# VHFA_PWR_Supply.net
KiCad netlist of a schematic drawn in Altium Designer
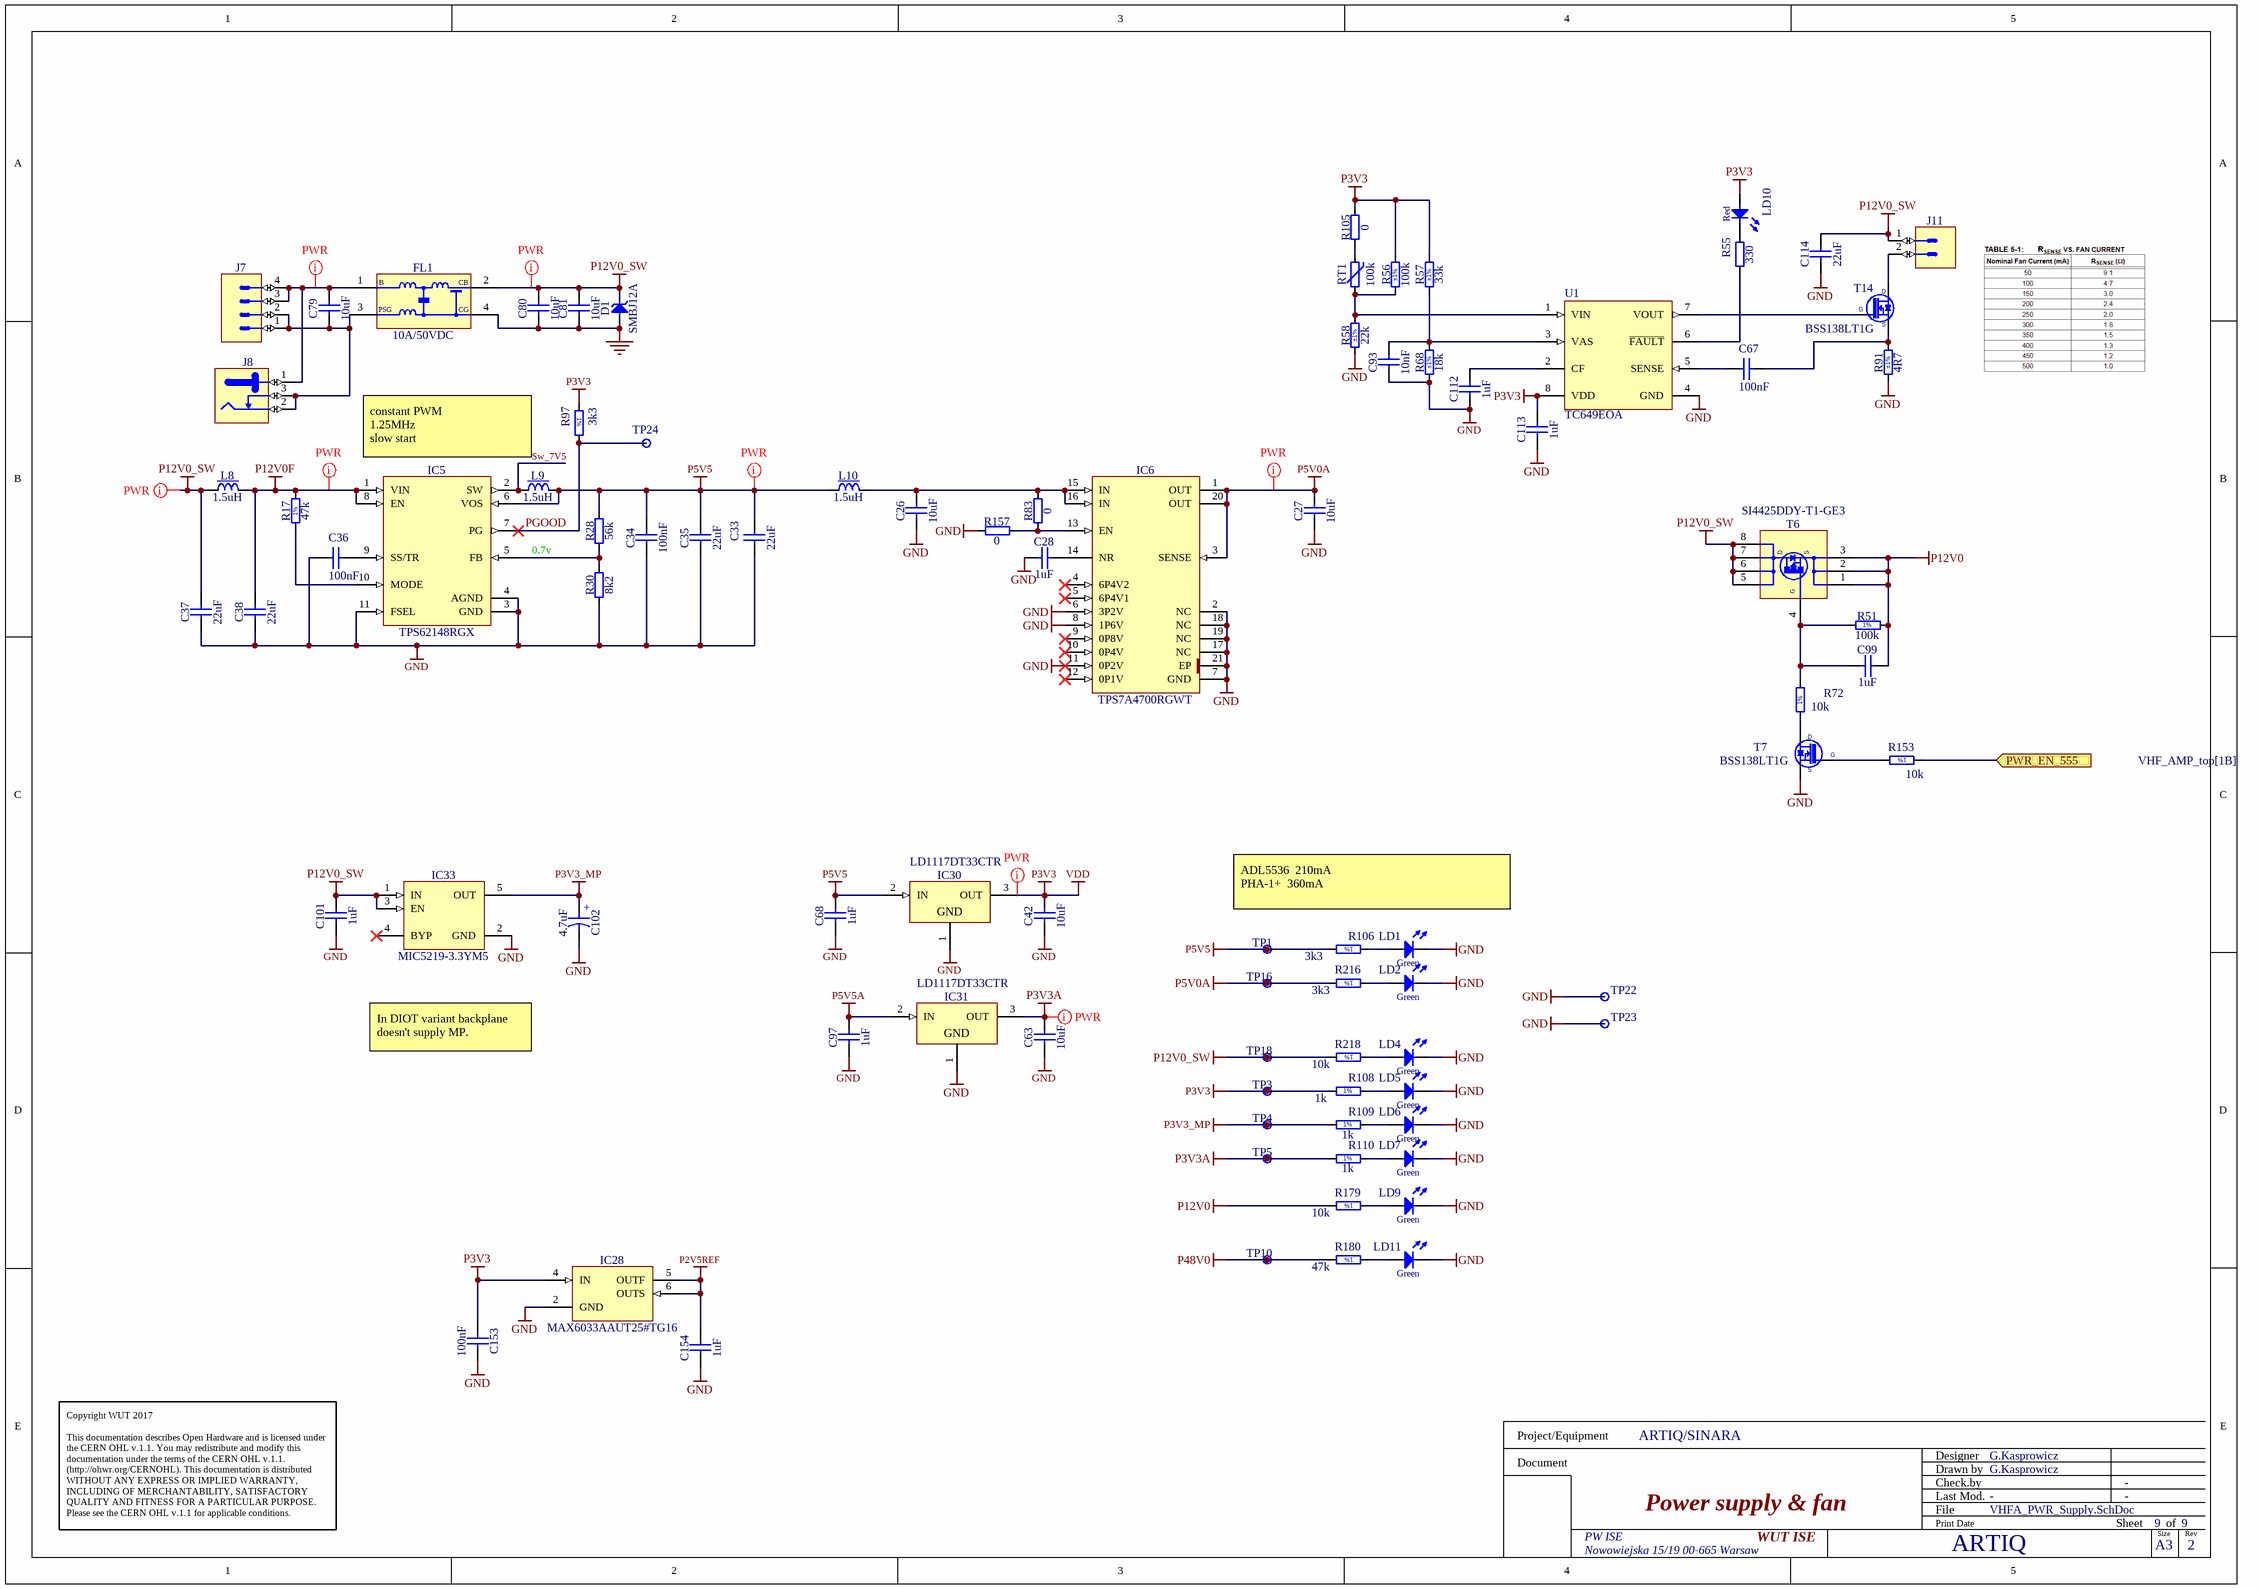
[diagram p0: VHFA_PWR_Supply.SchDoc]

(export (version "E")
  (design (tool "Eeschema 10.0.6"))
  (components
    (comp (ref "C26")
      (value "10uF")
      (footprint "CAPC3216X140N")
      (description "Non-polarised capacitor")
      (fields
        (field (name "PART NUMBER") "CC1206_10UF_10V_10%_X7R")
        (field (name "VOLTAGE") "10V")
        (field (name "AUTHOR") "CERN DEM JLC")
      )
      (libsource (lib "Capacitors") (part "Capacitor - non polarized"))
    )
    (comp (ref "C27")
      (value "10uF")
      (footprint "CAPC3216X140N")
      (description "Non-polarised capacitor")
      (fields
        (field (name "PART NUMBER") "CC1206_10UF_10V_10%_X7R")
        (field (name "VOLTAGE") "10V")
        (field (name "AUTHOR") "CERN DEM JLC")
      )
      (libsource (lib "Capacitors") (part "Capacitor - non polarized"))
    )
    (comp (ref "C28")
      (value "1uF")
      (footprint "CAPC1608X87N")
      (description "Non-polarised capacitor")
      (fields
        (field (name "PART NUMBER") "CC0603_1UF_16V_10%_X7R")
        (field (name "VOLTAGE") "16V")
        (field (name "AUTHOR") "CERN DEM JLC")
      )
      (libsource (lib "Capacitors") (part "Capacitor - non polarized"))
    )
    (comp (ref "C33")
      (value "22uF")
      (footprint "CAPC3216X180N")
      (description "Non-polarised capacitor")
      (fields
        (field (name "PART NUMBER") "CC1206_22UF_35V_20%_JB_TDK_C3216JB1V226M160AC")
        (field (name "VOLTAGE") "35V")
        (field (name "AUTHOR") "CERN DEM JLC")
      )
      (libsource (lib "Capacitors") (part "Capacitor - non polarized"))
    )
    (comp (ref "C34")
      (value "100nF")
      (footprint "CAPC1005X55N")
      (description "Non-polarised capacitor")
      (fields
        (field (name "PART NUMBER") "CC0402_100NF_16V_10%_X5R")
        (field (name "VOLTAGE") "16V")
        (field (name "AUTHOR") "CERN DEM JLC")
      )
      (libsource (lib "Capacitors") (part "Capacitor - non polarized"))
    )
    (comp (ref "C35")
      (value "22uF")
      (footprint "CAPC3216X180N")
      (description "Non-polarised capacitor")
      (fields
        (field (name "PART NUMBER") "CC1206_22UF_35V_20%_JB_TDK_C3216JB1V226M160AC")
        (field (name "VOLTAGE") "35V")
        (field (name "AUTHOR") "CERN DEM JLC")
      )
      (libsource (lib "Capacitors") (part "Capacitor - non polarized"))
    )
    (comp (ref "C36")
      (value "100nF")
      (footprint "CAPC1005X55N")
      (description "Non-polarised capacitor")
      (fields
        (field (name "PART NUMBER") "CC0402_100NF_16V_10%_X5R")
        (field (name "VOLTAGE") "16V")
        (field (name "AUTHOR") "CERN DEM JLC")
      )
      (libsource (lib "Capacitors") (part "Capacitor - non polarized"))
    )
    (comp (ref "C37")
      (value "22uF")
      (footprint "CAPC3216X180N")
      (description "Non-polarised capacitor")
      (fields
        (field (name "PART NUMBER") "CC1206_22UF_35V_20%_JB_TDK_C3216JB1V226M160AC")
        (field (name "VOLTAGE") "35V")
        (field (name "AUTHOR") "CERN DEM JLC")
      )
      (libsource (lib "Capacitors") (part "Capacitor - non polarized"))
    )
    (comp (ref "C38")
      (value "22uF")
      (footprint "CAPC3216X180N")
      (description "Non-polarised capacitor")
      (fields
        (field (name "PART NUMBER") "CC1206_22UF_35V_20%_JB_TDK_C3216JB1V226M160AC")
        (field (name "VOLTAGE") "35V")
        (field (name "AUTHOR") "CERN DEM JLC")
      )
      (libsource (lib "Capacitors") (part "Capacitor - non polarized"))
    )
    (comp (ref "C42")
      (value "10uF")
      (footprint "CAPC3216X140N")
      (description "Non-polarised capacitor")
      (fields
        (field (name "PART NUMBER") "CC1206_10UF_10V_10%_X7R")
        (field (name "VOLTAGE") "10V")
        (field (name "AUTHOR") "CERN DEM JLC")
      )
      (libsource (lib "Capacitors") (part "Capacitor - non polarized"))
    )
    (comp (ref "C63")
      (value "10uF")
      (footprint "CAPC3216X140N")
      (description "Non-polarised capacitor")
      (fields
        (field (name "PART NUMBER") "CC1206_10UF_10V_10%_X7R")
        (field (name "VOLTAGE") "10V")
        (field (name "AUTHOR") "CERN DEM JLC")
      )
      (libsource (lib "Capacitors") (part "Capacitor - non polarized"))
    )
    (comp (ref "C67")
      (value "100nF")
      (footprint "CAPC1005X55N")
      (description "Non-polarised capacitor")
      (fields
        (field (name "PART NUMBER") "CC0402_100NF_16V_10%_X5R")
        (field (name "VOLTAGE") "16V")
        (field (name "AUTHOR") "CERN DEM JLC")
      )
      (libsource (lib "Capacitors") (part "Capacitor - non polarized"))
    )
    (comp (ref "C68")
      (value "1uF")
      (footprint "CAPC1608X87N")
      (description "Non-polarised capacitor")
      (fields
        (field (name "PART NUMBER") "CC0603_1UF_16V_10%_X7R")
        (field (name "VOLTAGE") "16V")
        (field (name "AUTHOR") "CERN DEM JLC")
      )
      (libsource (lib "Capacitors") (part "Capacitor - non polarized"))
    )
    (comp (ref "C79")
      (value "10uF")
      (footprint "CAPC2012X95N")
      (description "Non-polarised capacitor")
      (fields
        (field (name "PART NUMBER") "CC0805_10UF_25V_10%_X5R")
        (field (name "VOLTAGE") "25V")
        (field (name "AUTHOR") "CERN DEM JLC")
      )
      (libsource (lib "Capacitors") (part "Capacitor - non polarized"))
    )
    (comp (ref "C80")
      (value "10uF")
      (footprint "CAPC2012X95N")
      (description "Non-polarised capacitor")
      (fields
        (field (name "PART NUMBER") "CC0805_10UF_25V_10%_X5R")
        (field (name "VOLTAGE") "25V")
        (field (name "AUTHOR") "CERN DEM JLC")
      )
      (libsource (lib "Capacitors") (part "Capacitor - non polarized"))
    )
    (comp (ref "C81")
      (value "10uF")
      (footprint "CAPC2012X95N")
      (description "Non-polarised capacitor")
      (fields
        (field (name "PART NUMBER") "CC0805_10UF_25V_10%_X5R")
        (field (name "VOLTAGE") "25V")
        (field (name "AUTHOR") "CERN DEM JLC")
      )
      (libsource (lib "Capacitors") (part "Capacitor - non polarized"))
    )
    (comp (ref "C93")
      (value "10nF")
      (footprint "CAPC1608X87N")
      (description "Non-polarised capacitor")
      (fields
        (field (name "PART NUMBER") "CC0603_10NF_50V_10%_X7R")
        (field (name "VOLTAGE") "50V")
        (field (name "AUTHOR") "CERN DEM JLC")
      )
      (libsource (lib "Capacitors") (part "Capacitor - non polarized"))
    )
    (comp (ref "C97")
      (value "1uF")
      (footprint "CAPC1608X87N")
      (description "Non-polarised capacitor")
      (fields
        (field (name "PART NUMBER") "CC0603_1UF_16V_10%_X7R")
        (field (name "VOLTAGE") "16V")
        (field (name "AUTHOR") "CERN DEM JLC")
      )
      (libsource (lib "Capacitors") (part "Capacitor - non polarized"))
    )
    (comp (ref "C99")
      (value "1uF")
      (footprint "CAPC1005X55N")
      (description "Non-polarised capacitor")
      (fields
        (field (name "PART NUMBER") "CC0402_1UF_16V_10%_X5R")
        (field (name "VOLTAGE") "16V")
        (field (name "AUTHOR") "CERN DEM JLC")
      )
      (libsource (lib "Capacitors") (part "Capacitor - non polarized"))
    )
    (comp (ref "C101")
      (value "1uF")
      (footprint "CAPC1608X87N")
      (description "Non-polarised capacitor")
      (fields
        (field (name "PART NUMBER") "CC0603_1UF_25V_10%_X7R")
        (field (name "VOLTAGE") "25V")
        (field (name "AUTHOR") "CERN DEM JLC")
      )
      (libsource (lib "Capacitors") (part "Capacitor - non polarized"))
    )
    (comp (ref "C102")
      (value "4.7uF")
      (footprint "CAPMP3216X180N")
      (description "Polarised capacitor")
      (fields
        (field (name "PART NUMBER") "CTE3216-18_4.7UF_10V_10%_AVX_TPSA475K010T1400")
        (field (name "VOLTAGE") "10V")
        (field (name "AUTHOR") "CERN DEM JLC")
      )
      (libsource (lib "Capacitors") (part "Capacitor - polarized"))
    )
    (comp (ref "C112")
      (value "1uF")
      (footprint "CAPC1608X87N")
      (description "Non-polarised capacitor")
      (fields
        (field (name "PART NUMBER") "CC0603_1UF_16V_10%_X7R")
        (field (name "VOLTAGE") "16V")
        (field (name "AUTHOR") "CERN DEM JLC")
      )
      (libsource (lib "Capacitors") (part "Capacitor - non polarized"))
    )
    (comp (ref "C113")
      (value "1uF")
      (footprint "CAPC1608X87N")
      (description "Non-polarised capacitor")
      (fields
        (field (name "PART NUMBER") "CC0603_1UF_16V_10%_X7R")
        (field (name "VOLTAGE") "16V")
        (field (name "AUTHOR") "CERN DEM JLC")
      )
      (libsource (lib "Capacitors") (part "Capacitor - non polarized"))
    )
    (comp (ref "C114")
      (value "22uF")
      (footprint "CAPC3216X180N")
      (description "Non-polarised capacitor")
      (fields
        (field (name "PART NUMBER") "CC1206_22UF_35V_20%_JB_TDK_C3216JB1V226M160AC")
        (field (name "VOLTAGE") "35V")
        (field (name "AUTHOR") "CERN DEM JLC")
      )
      (libsource (lib "Capacitors") (part "Capacitor - non polarized"))
    )
    (comp (ref "C153")
      (value "100nF")
      (footprint "CAPC1005X55N")
      (description "Non-polarised capacitor")
      (fields
        (field (name "PART NUMBER") "CC0402_100NF_16V_10%_X5R")
        (field (name "VOLTAGE") "16V")
        (field (name "AUTHOR") "CERN DEM JLC")
      )
      (libsource (lib "Capacitors") (part "Capacitor - non polarized"))
    )
    (comp (ref "C154")
      (value "1uF")
      (footprint "CAPC2012X110N")
      (description "Non-polarised capacitor")
      (fields
        (field (name "PART NUMBER") "CC0805_1UF_50V_10%_X7R")
        (field (name "VOLTAGE") "50V")
        (field (name "AUTHOR") "CERN DEM JLC")
      )
      (libsource (lib "Capacitors") (part "Capacitor - non polarized"))
    )
    (comp (ref "D1")
      (value "SMBJ12A")
      (footprint "DIOM5336X265N")
      (description "Zener Diode")
      (fields
        (field (name "VOLTAGE") "12V")
        (field (name "POWER") "600W")
        (field (name "AUTHOR") "CERN DEM JLC")
      )
      (libsource (lib "ICs And Semiconductors") (part "Diode Zener"))
    )
    (comp (ref "FL1")
      (value "10A/50VDC")
      (footprint "FIL_MURATA_BNX02")
      (description "Block Type EMIFIL (LC Combined)")
      (fields
        (field (name "PART NUMBER") "FIL_MURATA_BNX022-01L")
        (field (name "MANUFACTURER") "MURATA")
        (field (name "AUTHOR") "CERN DEM JLC")
      )
      (libsource (lib "Inductors & Transformers") (part "FIL_MURATA_BNX02"))
    )
    (comp (ref "IC5")
      (value "TPS62148RGX")
      (footprint "TEXAS_RGX0011A")
      (description "3V-17V 2A Step-Down Converter, High Accuracy, With DCS-Control")
      (fields (field (name "MANUFACTURER") "TEXAS INSTRUMENTS") (field (name "AUTHOR") "CERN DEM MR"))
      (libsource (lib "ICs And Semiconductors") (part "TPS62148"))
    )
    (comp (ref "IC6")
      (value "TPS7A4700RGWT")
      (footprint "QFN65P500X500X100-21N-S325")
      (description "Low Noise (3uVrms), 1A, High Voltage Low-Dropout Linear Regulator")
      (fields
        (field (name "MANUFACTURER") "TEXAS INSTRUMENTS")
        (field (name "MANUFACTURER PART NUMBER") "TPS7A4700RGW")
        (field (name "AUTHOR") "CERN DEM JLC")
      )
      (libsource (lib "ICs And Semiconductors") (part "TPS7A4700RGW"))
    )
    (comp (ref "IC28")
      (value "MAX6033AAUT25#TG16")
      (footprint "SOT95P280X145-6N")
      (description "Ultra-High-Precision Voltage References")
      (fields (field (name "MANUFACTURER") "MAXIM") (field (name "AUTHOR") "CERN DEM JLC"))
      (libsource (lib "ICs And Semiconductors") (part "MAX6033"))
    )
    (comp (ref "IC30")
      (value "LD1117DT33CTR")
      (footprint "TO228P972X240-3N-R540X510")
      (description "3-Terminal Regulator 1=GND 2=IN 3=OUT")
      (fields (field (name "MANUFACTURER") "ST MICROELECTRONICS") (field (name "AUTHOR") "CERN DEM JLC"))
      (libsource (lib "ICs And Semiconductors") (part "REG3 1GND-2IN-3OUT"))
    )
    (comp (ref "IC31")
      (value "LD1117DT33CTR")
      (footprint "TO228P972X240-3N-R540X510")
      (description "3-Terminal Regulator 1=GND 2=IN 3=OUT")
      (fields (field (name "MANUFACTURER") "ST MICROELECTRONICS") (field (name "AUTHOR") "CERN DEM JLC"))
      (libsource (lib "ICs And Semiconductors") (part "REG3 1GND-2IN-3OUT"))
    )
    (comp (ref "IC33")
      (value "MIC5219-3.3YM5")
      (footprint "SOT95P280X145-5N")
      (description "500mA Peak Output LDO Regulator")
      (fields (field (name "MANUFACTURER") "MICROCHIP TECHNOLOGY") (field (name "AUTHOR") "CERN DEM WB"))
      (libsource (lib "ICs And Semiconductors") (part "MIC5219-X.XYM5"))
    )
    (comp (ref "J7")
      (value "Mini-Fit Jr.™")
      (footprint "MOLEX_39-30-0040")
      (description "Connector 4 Male")
      (fields
        (field (name "PART NUMBER") "MOLEX_39-30-0040")
        (field (name "MANUFACTURER") "MOLEX")
        (field (name "AUTHOR") "CERN DEM JLC")
      )
      (libsource (lib "Connectors") (part "Connector 4 Male"))
    )
    (comp (ref "J8")
      (value "Jack")
      (footprint "SWITCHCRAFT_712RA")
      (description "2.5 mm Center Pin, 5A, 48V, Right Angle, Through Hole, , DC Power Jack Connector")
      (fields
        (field (name "PART NUMBER") "SWITCHCRAFT_712RA")
        (field (name "MANUFACTURER") "SWITCHCRAFT")
        (field (name "AUTHOR") "CERN DEM JLC")
      )
      (libsource (lib "Connectors") (part "SWITCHCRAFT_712RA"))
    )
    (comp (ref "J11")
      (value "KK®")
      (footprint "MOLEX_22-04-1021")
      (description "Connector 2 Male")
      (fields
        (field (name "PART NUMBER") "MOLEX_22-04-1021")
        (field (name "MANUFACTURER") "MOLEX")
        (field (name "AUTHOR") "CERN DEM JLC")
      )
      (libsource (lib "Connectors") (part "Connector 2 Male"))
    )
    (comp (ref "L8")
      (value "1.5uH")
      (footprint "IND_TDK_SPM6530")
      (description "Inductor With Core")
      (fields
        (field (name "PART NUMBER") "IND_1.5UH_20%_TDK_SPM6530")
        (field (name "POWER") "11A")
        (field (name "AUTHOR") "CERN DEM MR")
      )
      (libsource (lib "Inductors & Transformers") (part "Inductor With Magnetic core"))
    )
    (comp (ref "L9")
      (value "1.5uH")
      (footprint "IND_TDK_SPM6530")
      (description "Inductor With Core")
      (fields
        (field (name "PART NUMBER") "IND_1.5UH_20%_TDK_SPM6530")
        (field (name "POWER") "11A")
        (field (name "AUTHOR") "CERN DEM MR")
      )
      (libsource (lib "Inductors & Transformers") (part "Inductor With Magnetic core"))
    )
    (comp (ref "L10")
      (value "1.5uH")
      (footprint "IND_TDK_SPM6530")
      (description "Inductor With Core")
      (fields
        (field (name "PART NUMBER") "IND_1.5UH_20%_TDK_SPM6530")
        (field (name "POWER") "11A")
        (field (name "AUTHOR") "CERN DEM MR")
      )
      (libsource (lib "Inductors & Transformers") (part "Inductor With Magnetic core"))
    )
    (comp (ref "LD1")
      (value "Green")
      (footprint "LED_KINGBRIGHT_KPH-1608CGCK")
      (description "LED Green 1C 2A")
      (fields
        (field (name "PART NUMBER") "LED_KINGBRIGHT_KPH-1608CGCK")
        (field (name "MANUFACTURER") "KINGBRIGHT")
        (field (name "AUTHOR") "CERN DEM JLC")
      )
      (libsource (lib "ICs And Semiconductors") (part "LED Green 1C 2A"))
    )
    (comp (ref "LD2")
      (value "Green")
      (footprint "LED_KINGBRIGHT_KPH-1608CGCK")
      (description "LED Green 1C 2A")
      (fields
        (field (name "PART NUMBER") "LED_KINGBRIGHT_KPH-1608CGCK")
        (field (name "MANUFACTURER") "KINGBRIGHT")
        (field (name "AUTHOR") "CERN DEM JLC")
      )
      (libsource (lib "ICs And Semiconductors") (part "LED Green 1C 2A"))
    )
    (comp (ref "LD4")
      (value "Green")
      (footprint "LED_KINGBRIGHT_KPH-1608CGCK")
      (description "LED Green 1C 2A")
      (fields
        (field (name "PART NUMBER") "LED_KINGBRIGHT_KPH-1608CGCK")
        (field (name "MANUFACTURER") "KINGBRIGHT")
        (field (name "AUTHOR") "CERN DEM JLC")
      )
      (libsource (lib "ICs And Semiconductors") (part "LED Green 1C 2A"))
    )
    (comp (ref "LD5")
      (value "Green")
      (footprint "LED_KINGBRIGHT_KPH-1608CGCK")
      (description "LED Green 1C 2A")
      (fields
        (field (name "PART NUMBER") "LED_KINGBRIGHT_KPH-1608CGCK")
        (field (name "MANUFACTURER") "KINGBRIGHT")
        (field (name "AUTHOR") "CERN DEM JLC")
      )
      (libsource (lib "ICs And Semiconductors") (part "LED Green 1C 2A"))
    )
    (comp (ref "LD6")
      (value "Green")
      (footprint "LED_KINGBRIGHT_KPH-1608CGCK")
      (description "LED Green 1C 2A")
      (fields
        (field (name "PART NUMBER") "LED_KINGBRIGHT_KPH-1608CGCK")
        (field (name "MANUFACTURER") "KINGBRIGHT")
        (field (name "AUTHOR") "CERN DEM JLC")
      )
      (libsource (lib "ICs And Semiconductors") (part "LED Green 1C 2A"))
    )
    (comp (ref "LD7")
      (value "Green")
      (footprint "LED_KINGBRIGHT_KPH-1608CGCK")
      (description "LED Green 1C 2A")
      (fields
        (field (name "PART NUMBER") "LED_KINGBRIGHT_KPH-1608CGCK")
        (field (name "MANUFACTURER") "KINGBRIGHT")
        (field (name "AUTHOR") "CERN DEM JLC")
      )
      (libsource (lib "ICs And Semiconductors") (part "LED Green 1C 2A"))
    )
    (comp (ref "LD9")
      (value "Green")
      (footprint "LED_KINGBRIGHT_KPH-1608CGCK")
      (description "LED Green 1C 2A")
      (fields
        (field (name "PART NUMBER") "LED_KINGBRIGHT_KPH-1608CGCK")
        (field (name "MANUFACTURER") "KINGBRIGHT")
        (field (name "AUTHOR") "CERN DEM JLC")
      )
      (libsource (lib "ICs And Semiconductors") (part "LED Green 1C 2A"))
    )
    (comp (ref "LD10")
      (value "Red")
      (footprint "LED_AVAGO_HSMC-C120")
      (description "LED Red 1C 2A")
      (fields
        (field (name "PART NUMBER") "LED_AVAGO_HSMC-C120")
        (field (name "MANUFACTURER") "AVAGO TECHNOLOGIES")
        (field (name "AUTHOR") "CERN DEM JMW")
      )
      (libsource (lib "ICs And Semiconductors") (part "LED Red 1C 2A"))
    )
    (comp (ref "LD11")
      (value "Green")
      (footprint "LED_KINGBRIGHT_KPH-1608CGCK")
      (description "LED Green 1C 2A")
      (fields
        (field (name "PART NUMBER") "LED_KINGBRIGHT_KPH-1608CGCK")
        (field (name "MANUFACTURER") "KINGBRIGHT")
        (field (name "AUTHOR") "CERN DEM JLC")
      )
      (libsource (lib "ICs And Semiconductors") (part "LED Green 1C 2A"))
    )
    (comp (ref "R17")
      (value "47k")
      (footprint "RESC1608X55N")
      (description "Resistor - 1%")
      (fields
        (field (name "PART NUMBER") "R0603_47K_1%_0.1W_100PPM")
        (field (name "POWER") "0.1W")
        (field (name "AUTHOR") "CERN DEM JLC")
      )
      (libsource (lib "Resistors") (part "Resistor - 1%"))
    )
    (comp (ref "R28")
      (value "56k")
      (footprint "RESC1608X55N")
      (description "Resistor - 1%")
      (fields
        (field (name "PART NUMBER") "R0603_56K_1%_0.1W_100PPM")
        (field (name "POWER") "0.1W")
        (field (name "AUTHOR") "CERN DEM JLC")
      )
      (libsource (lib "Resistors") (part "Resistor - 1%"))
    )
    (comp (ref "R30")
      (value "8k2")
      (footprint "RESC1608X55N")
      (description "Resistor - 1%")
      (fields
        (field (name "PART NUMBER") "R0603_8K2_1%_0.1W_100PPM")
        (field (name "POWER") "0.1W")
        (field (name "AUTHOR") "CERN DEM JLC")
      )
      (libsource (lib "Resistors") (part "Resistor - 1%"))
    )
    (comp (ref "R51")
      (value "100k")
      (footprint "RESC1608X55N")
      (description "Resistor - 1%")
      (fields
        (field (name "PART NUMBER") "R0603_100K_1%_0.1W_100PPM")
        (field (name "POWER") "0.1W")
        (field (name "AUTHOR") "CERN DEM JLC")
      )
      (libsource (lib "Resistors") (part "Resistor - 1%"))
    )
    (comp (ref "R55")
      (value "330")
      (footprint "RESC1005X40N")
      (description "Resistor - 1%")
      (fields
        (field (name "PART NUMBER") "R0402_330R_1%_0.0625W_100PPM")
        (field (name "POWER") "0.0625W")
        (field (name "AUTHOR") "CERN DEM JLC")
      )
      (libsource (lib "") (part "Resistor - 1%_1"))
    )
    (comp (ref "R56")
      (value "100k")
      (footprint "RESC1005X40N")
      (description "Resistor - 1%")
      (fields
        (field (name "TOLERANCE") "±1%")
        (field (name "PART NUMBER") "R0402_100K_1%_0.0625W_100PPM")
        (field (name "POWER") "0.0625W")
        (field (name "AUTHOR") "CERN DEM JLC")
      )
      (libsource (lib "") (part "Resistor - 1%_1"))
    )
    (comp (ref "R57")
      (value "33k")
      (footprint "RESC1005X40N")
      (description "Resistor - 1%")
      (fields
        (field (name "TOLERANCE") "±1%")
        (field (name "PART NUMBER") "R0402_33K_1%_0.0625W_100PPM")
        (field (name "POWER") "0.0625W")
        (field (name "AUTHOR") "CERN DEM JLC")
      )
      (libsource (lib "") (part "Resistor - 1%_1"))
    )
    (comp (ref "R58")
      (value "22k")
      (footprint "RESC1005X40N")
      (description "Resistor - 1%")
      (fields
        (field (name "TOLERANCE") "±1%")
        (field (name "PART NUMBER") "R0402_22K_1%_0.0625W_100PPM")
        (field (name "POWER") "0.0625W")
        (field (name "AUTHOR") "CERN DEM JLC")
      )
      (libsource (lib "") (part "Resistor - 1%_1"))
    )
    (comp (ref "R68")
      (value "18k")
      (footprint "RESC1005X40N")
      (description "Resistor - 1%")
      (fields
        (field (name "TOLERANCE") "±1%")
        (field (name "PART NUMBER") "R0402_18K_1%_0.0625W_100PPM")
        (field (name "POWER") "0.0625W")
        (field (name "AUTHOR") "CERN DEM JLC")
      )
      (libsource (lib "") (part "Resistor - 1%_1"))
    )
    (comp (ref "R72")
      (value "10k")
      (footprint "RESC1005X40N")
      (description "Resistor - 1%")
      (fields
        (field (name "PART NUMBER") "R0402_10K_1%_0.0625W_100PPM")
        (field (name "POWER") "0.0625W")
        (field (name "AUTHOR") "CERN DEM JLC")
      )
      (libsource (lib "Resistors") (part "Resistor - 1%"))
    )
    (comp (ref "R83")
      (value "0")
      (footprint "RESC1608X55N")
      (description "Resistor")
      (fields
        (field (name "PART NUMBER") "R0603_0R_JUMPER")
        (field (name "MANUFACTURER") "GENERIC")
        (field (name "AUTHOR") "CERN DEM JLC")
      )
      (libsource (lib "Resistors") (part "Resistor"))
    )
    (comp (ref "R91")
      (value "4R7")
      (footprint "RESC2012X60N")
      (description "Resistor - 1%")
      (fields
        (field (name "TOLERANCE") "±1%")
        (field (name "PART NUMBER") "R0805_4R7_1%_0.125W_200PPM")
        (field (name "POWER") "0.125W")
        (field (name "AUTHOR") "CERN DEM JLC")
      )
      (libsource (lib "") (part "Resistor - 1%_1"))
    )
    (comp (ref "R97")
      (value "3k3")
      (footprint "RESC1608X55N")
      (description "Resistor - 1%")
      (fields
        (field (name "PART NUMBER") "R0603_3K3_1%_0.1W_100PPM")
        (field (name "POWER") "0.1W")
        (field (name "AUTHOR") "CERN DEM JLC")
      )
      (libsource (lib "Resistors") (part "Resistor - 1%"))
    )
    (comp (ref "R105")
      (value "0")
      (footprint "RESC1005X40N")
      (description "Resistor")
      (fields
        (field (name "PART NUMBER") "R0402_0R_JUMPER")
        (field (name "MANUFACTURER") "GENERIC")
        (field (name "AUTHOR") "CERN DEM JLC")
      )
      (libsource (lib "Resistors") (part "Resistor"))
    )
    (comp (ref "R106")
      (value "3k3")
      (footprint "RESC1608X55N")
      (description "Resistor - 1%")
      (fields
        (field (name "PART NUMBER") "R0603_3K3_1%_0.1W_100PPM")
        (field (name "POWER") "0.1W")
        (field (name "AUTHOR") "CERN DEM JLC")
      )
      (libsource (lib "Resistors") (part "Resistor - 1%"))
    )
    (comp (ref "R108")
      (value "1k")
      (footprint "RESC1608X55N")
      (description "Resistor - 1%")
      (fields
        (field (name "MANUFACTURER") "GENERIC")
        (field (name "MANUFACTURER PART NUMBER") "R0603_1K_1%_0.1W_100PPM")
        (field (name "AUTHOR") "CERN DEM JLC")
      )
      (libsource (lib "Resistors") (part "Resistor - 1%"))
    )
    (comp (ref "R109")
      (value "1k")
      (footprint "RESC1608X55N")
      (description "Resistor - 1%")
      (fields
        (field (name "MANUFACTURER") "GENERIC")
        (field (name "MANUFACTURER PART NUMBER") "R0603_1K_1%_0.1W_100PPM")
        (field (name "AUTHOR") "CERN DEM JLC")
      )
      (libsource (lib "Resistors") (part "Resistor - 1%"))
    )
    (comp (ref "R110")
      (value "1k")
      (footprint "RESC1608X55N")
      (description "Resistor - 1%")
      (fields
        (field (name "MANUFACTURER") "GENERIC")
        (field (name "MANUFACTURER PART NUMBER") "R0603_1K_1%_0.1W_100PPM")
        (field (name "AUTHOR") "CERN DEM JLC")
      )
      (libsource (lib "Resistors") (part "Resistor - 1%"))
    )
    (comp (ref "R153")
      (value "10k")
      (footprint "RESC1005X40N")
      (description "Resistor - 1%")
      (fields
        (field (name "PART NUMBER") "R0402_10K_1%_0.0625W_100PPM")
        (field (name "POWER") "0.0625W")
        (field (name "AUTHOR") "CERN DEM JLC")
      )
      (libsource (lib "Resistors") (part "Resistor - 1%"))
    )
    (comp (ref "R157")
      (value "0")
      (footprint "RESC1608X55N")
      (description "Resistor")
      (fields
        (field (name "PART NUMBER") "R0603_0R_JUMPER")
        (field (name "MANUFACTURER") "GENERIC")
        (field (name "AUTHOR") "CERN DEM JLC")
      )
      (libsource (lib "Resistors") (part "Resistor"))
    )
    (comp (ref "R179")
      (value "10k")
      (footprint "RESC1005X40N")
      (description "Resistor - 1%")
      (fields
        (field (name "PART NUMBER") "R0402_10K_1%_0.0625W_100PPM")
        (field (name "POWER") "0.0625W")
        (field (name "AUTHOR") "CERN DEM JLC")
      )
      (libsource (lib "Resistors") (part "Resistor - 1%"))
    )
    (comp (ref "R180")
      (value "47k")
      (footprint "RESC1005X40N")
      (description "Resistor - 1%")
      (fields
        (field (name "PART NUMBER") "R0402_47K_1%_0.0625W_100PPM")
        (field (name "POWER") "0.0625W")
        (field (name "AUTHOR") "CERN DEM JLC")
      )
      (libsource (lib "Resistors") (part "Resistor - 1%"))
    )
    (comp (ref "R216")
      (value "3k3")
      (footprint "RESC1608X55N")
      (description "Resistor - 1%")
      (fields
        (field (name "PART NUMBER") "R0603_3K3_1%_0.1W_100PPM")
        (field (name "POWER") "0.1W")
        (field (name "AUTHOR") "CERN DEM JLC")
      )
      (libsource (lib "Resistors") (part "Resistor - 1%"))
    )
    (comp (ref "R218")
      (value "10k")
      (footprint "RESC1005X40N")
      (description "Resistor - 1%")
      (fields
        (field (name "PART NUMBER") "R0402_10K_1%_0.0625W_100PPM")
        (field (name "POWER") "0.0625W")
        (field (name "AUTHOR") "CERN DEM JLC")
      )
      (libsource (lib "Resistors") (part "Resistor - 1%"))
    )
    (comp (ref "RT1")
      (value "100k")
      (footprint "THERMC1608X95N")
      (description "Thermistor NTC (Negative Temperature Coefficient)")
      (fields
        (field (name "PART NUMBER") "THERM_NTC_100K_VISHAY_NTCS0603E3104FXT")
        (field (name "POWER") "125mW")
        (field (name "AUTHOR") "CERN DEM JMW")
      )
      (libsource (lib "Resistors") (part "Thermistor NTC"))
    )
    (comp (ref "T6")
      (value "SI4425DDY-T1-GE3")
      (footprint "SOIC127P600X175-8N")
      (description "-30V -19.7A P-Channel MOSFET")
      (fields (field (name "MANUFACTURER") "VISHAY SILICONIX") (field (name "AUTHOR") "CERN DEM MR"))
      (libsource (lib "ICs And Semiconductors") (part "SI4425DDY"))
    )
    (comp (ref "T7")
      (value "BSS138LT1G")
      (footprint "SOT95P240X110-3N")
      (description "N-CHANNEL MOSFET WITH DIODE")
      (fields (field (name "MANUFACTURER") "ON SEMICONDUCTOR") (field (name "AUTHOR") "CERN DEM JLC"))
      (libsource (lib "ICs And Semiconductors") (part "N-MOSFET-D 1G 2S 3D"))
    )
    (comp (ref "T14")
      (value "BSS138LT1G")
      (footprint "SOT95P240X110-3N")
      (description "N-CHANNEL MOSFET WITH DIODE")
      (fields (field (name "MANUFACTURER") "ON SEMICONDUCTOR") (field (name "AUTHOR") "CERN DEM JLC"))
      (libsource (lib "") (part "N-MOSFET-D 1G 2S 3D_1"))
    )
    (comp (ref "TP1")
      (value "Test Point")
      (footprint "TPS127")
      (fields (field (name "PART NUMBER") "SMD_PAD_1.27X1.27MM") (field (name "AUTHOR") "CERN DEM JLC"))
      (libsource (lib "Eletro-mechanical") (part "Test Point"))
    )
    (comp (ref "TP3")
      (value "Test Point")
      (footprint "TPS127")
      (fields (field (name "PART NUMBER") "SMD_PAD_1.27X1.27MM") (field (name "AUTHOR") "CERN DEM JLC"))
      (libsource (lib "Eletro-mechanical") (part "Test Point"))
    )
    (comp (ref "TP4")
      (value "Test Point")
      (footprint "TPS127")
      (fields (field (name "PART NUMBER") "SMD_PAD_1.27X1.27MM") (field (name "AUTHOR") "CERN DEM JLC"))
      (libsource (lib "Eletro-mechanical") (part "Test Point"))
    )
    (comp (ref "TP5")
      (value "Test Point")
      (footprint "TPS127")
      (fields (field (name "PART NUMBER") "SMD_PAD_1.27X1.27MM") (field (name "AUTHOR") "CERN DEM JLC"))
      (libsource (lib "Eletro-mechanical") (part "Test Point"))
    )
    (comp (ref "TP10")
      (value "Test Point")
      (footprint "TPS127")
      (fields (field (name "PART NUMBER") "SMD_PAD_1.27X1.27MM") (field (name "AUTHOR") "CERN DEM JLC"))
      (libsource (lib "Eletro-mechanical") (part "Test Point"))
    )
    (comp (ref "TP16")
      (value "Test Point")
      (footprint "TPS127")
      (fields (field (name "PART NUMBER") "SMD_PAD_1.27X1.27MM") (field (name "AUTHOR") "CERN DEM JLC"))
      (libsource (lib "Eletro-mechanical") (part "Test Point"))
    )
    (comp (ref "TP18")
      (value "Test Point")
      (footprint "TPS127")
      (fields (field (name "PART NUMBER") "SMD_PAD_1.27X1.27MM") (field (name "AUTHOR") "CERN DEM JLC"))
      (libsource (lib "Eletro-mechanical") (part "Test Point"))
    )
    (comp (ref "TP22")
      (value "Test Point")
      (footprint "TPS127")
      (fields (field (name "PART NUMBER") "SMD_PAD_1.27X1.27MM") (field (name "AUTHOR") "CERN DEM JLC"))
      (libsource (lib "Eletro-mechanical") (part "Test Point"))
    )
    (comp (ref "TP23")
      (value "Test Point")
      (footprint "TPS127")
      (fields (field (name "PART NUMBER") "SMD_PAD_1.27X1.27MM") (field (name "AUTHOR") "CERN DEM JLC"))
      (libsource (lib "Eletro-mechanical") (part "Test Point"))
    )
    (comp (ref "TP24")
      (value "Test Point")
      (footprint "NICOMATIC_C12000B")
      (fields
        (field (name "PART NUMBER") "NICOMATIC_C12000B")
        (field (name "MANUFACTURER") "NICOMATIC")
        (field (name "MANUFACTURER PART NUMBER") "C12000B")
        (field (name "AUTHOR") "CERN DEM JLC")
      )
      (libsource (lib "Connectors") (part "Test Point"))
    )
    (comp (ref "U1")
      (value "TC649EOA")
      (footprint "SOIC127P600X175-8N")
      (libsource (lib "VHF_AMP_lib") (part "TC649EOA"))
    )
  )
  (nets
    (net (code "1") (name "/PGOOD") (class "Default")
      (node (ref "IC5") (pin "7") (pinfunction "PG_7") (pintype "output"))
      (node (ref "R97") (pin "2") (pinfunction "2_2") (pintype "passive"))
      (node (ref "TP24") (pin "1") (pinfunction "1_1") (pintype "bidirectional"))
    )
    (net (code "2") (name "/PWR_EN_555") (class "Default")
      (node (ref "R153") (pin "1") (pinfunction "1_1") (pintype "passive"))
    )
    (net (code "3") (name "/Sw_7V5") (class "Default")
      (node (ref "IC5") (pin "2") (pinfunction "SW_2") (pintype "output"))
      (node (ref "L9") (pin "1") (pinfunction "1_1") (pintype "passive"))
    )
    (net (code "4") (name "GND") (class "Default")
      (node (ref "C101") (pin "1") (pinfunction "1_1") (pintype "passive"))
      (node (ref "C102") (pin "2") (pinfunction "2_2") (pintype "passive"))
      (node (ref "C112") (pin "1") (pinfunction "1_1") (pintype "passive"))
      (node (ref "C113") (pin "1") (pinfunction "1_1") (pintype "passive"))
      (node (ref "C114") (pin "1") (pinfunction "1_1") (pintype "passive"))
      (node (ref "C153") (pin "2") (pinfunction "2_2") (pintype "passive"))
      (node (ref "C154") (pin "1") (pinfunction "1_1") (pintype "passive"))
      (node (ref "C26") (pin "1") (pinfunction "1_1") (pintype "passive"))
      (node (ref "C27") (pin "1") (pinfunction "1_1") (pintype "passive"))
      (node (ref "C28") (pin "1") (pinfunction "1_1") (pintype "passive"))
      (node (ref "C33") (pin "1") (pinfunction "1_1") (pintype "passive"))
      (node (ref "C34") (pin "1") (pinfunction "1_1") (pintype "passive"))
      (node (ref "C35") (pin "1") (pinfunction "1_1") (pintype "passive"))
      (node (ref "C36") (pin "2") (pinfunction "2_2") (pintype "passive"))
      (node (ref "C37") (pin "1") (pinfunction "1_1") (pintype "passive"))
      (node (ref "C38") (pin "1") (pinfunction "1_1") (pintype "passive"))
      (node (ref "C42") (pin "1") (pinfunction "1_1") (pintype "passive"))
      (node (ref "C63") (pin "1") (pinfunction "1_1") (pintype "passive"))
      (node (ref "C68") (pin "1") (pinfunction "1_1") (pintype "passive"))
      (node (ref "C80") (pin "1") (pinfunction "1_1") (pintype "passive"))
      (node (ref "C81") (pin "1") (pinfunction "1_1") (pintype "passive"))
      (node (ref "C93") (pin "1") (pinfunction "1_1") (pintype "passive"))
      (node (ref "C97") (pin "1") (pinfunction "1_1") (pintype "passive"))
      (node (ref "D1") (pin "2") (pinfunction "A_2") (pintype "passive"))
      (node (ref "FL1") (pin "4") (pinfunction "CG_4") (pintype "passive"))
      (node (ref "IC28") (pin "2") (pinfunction "GND_2") (pintype "power_in"))
      (node (ref "IC30") (pin "1") (pinfunction "GND_1") (pintype "power_in"))
      (node (ref "IC31") (pin "1") (pinfunction "GND_1") (pintype "power_in"))
      (node (ref "IC33") (pin "2") (pinfunction "GND_2") (pintype "power_in"))
      (node (ref "IC5") (pin "11") (pinfunction "FSEL_11") (pintype "input"))
      (node (ref "IC5") (pin "3") (pinfunction "GND_3") (pintype "power_in"))
      (node (ref "IC5") (pin "4") (pinfunction "AGND_4") (pintype "power_in"))
      (node (ref "IC6") (pin "11") (pinfunction "0P2V_11") (pintype "input"))
      (node (ref "IC6") (pin "17") (pinfunction "NC_17") (pintype "passive"))
      (node (ref "IC6") (pin "18") (pinfunction "NC_18") (pintype "passive"))
      (node (ref "IC6") (pin "19") (pinfunction "NC_19") (pintype "passive"))
      (node (ref "IC6") (pin "2") (pinfunction "NC_2") (pintype "passive"))
      (node (ref "IC6") (pin "21") (pinfunction "EP_21") (pintype "power_in"))
      (node (ref "IC6") (pin "6") (pinfunction "3P2V_6") (pintype "input"))
      (node (ref "IC6") (pin "7") (pinfunction "GND_7") (pintype "power_in"))
      (node (ref "IC6") (pin "8") (pinfunction "1P6V_8") (pintype "input"))
      (node (ref "LD1") (pin "1") (pinfunction "C_1") (pintype "passive"))
      (node (ref "LD11") (pin "1") (pinfunction "C_1") (pintype "passive"))
      (node (ref "LD2") (pin "1") (pinfunction "C_1") (pintype "passive"))
      (node (ref "LD4") (pin "1") (pinfunction "C_1") (pintype "passive"))
      (node (ref "LD5") (pin "1") (pinfunction "C_1") (pintype "passive"))
      (node (ref "LD6") (pin "1") (pinfunction "C_1") (pintype "passive"))
      (node (ref "LD7") (pin "1") (pinfunction "C_1") (pintype "passive"))
      (node (ref "LD9") (pin "1") (pinfunction "C_1") (pintype "passive"))
      (node (ref "R157") (pin "1") (pinfunction "1_1") (pintype "passive"))
      (node (ref "R30") (pin "1") (pinfunction "1_1") (pintype "passive"))
      (node (ref "R58") (pin "1") (pinfunction "1_1") (pintype "passive"))
      (node (ref "R68") (pin "1") (pinfunction "1_1") (pintype "passive"))
      (node (ref "R91") (pin "1") (pinfunction "1_1") (pintype "passive"))
      (node (ref "T7") (pin "2") (pinfunction "S_2") (pintype "passive"))
      (node (ref "TP22") (pin "1") (pinfunction "1_1") (pintype "bidirectional"))
      (node (ref "TP23") (pin "1") (pinfunction "1_1") (pintype "bidirectional"))
      (node (ref "U1") (pin "4") (pinfunction "GND_4") (pintype "power_in"))
    )
    (net (code "5") (name "Net-(C26-Pad2)") (class "Default")
      (node (ref "C26") (pin "2") (pinfunction "2_2") (pintype "passive"))
      (node (ref "IC6") (pin "15") (pinfunction "IN_15") (pintype "input"))
      (node (ref "IC6") (pin "16") (pinfunction "IN_16") (pintype "input"))
      (node (ref "L10") (pin "2") (pinfunction "2_2") (pintype "passive"))
      (node (ref "R83") (pin "2") (pinfunction "2_2") (pintype "passive"))
    )
    (net (code "6") (name "Net-(C99-Pad1)") (class "Default")
      (node (ref "C99") (pin "1") (pinfunction "1_1") (pintype "passive"))
      (node (ref "R51") (pin "1") (pinfunction "1_1") (pintype "passive"))
      (node (ref "R72") (pin "2") (pinfunction "2_2") (pintype "passive"))
      (node (ref "T6") (pin "4") (pinfunction "S_4") (pintype "passive"))
    )
    (net (code "7") (name "Net-(FL1-B)") (class "Default")
      (node (ref "C79") (pin "2") (pinfunction "2_2") (pintype "passive"))
      (node (ref "FL1") (pin "1") (pinfunction "B_1") (pintype "passive"))
      (node (ref "J7") (pin "3") (pinfunction "3_3") (pintype "bidirectional"))
      (node (ref "J7") (pin "4") (pinfunction "4_4") (pintype "bidirectional"))
      (node (ref "J8") (pin "1") (pinfunction "1_1") (pintype "bidirectional"))
    )
    (net (code "8") (name "Net-(FL1-PSG)") (class "Default")
      (node (ref "C79") (pin "1") (pinfunction "1_1") (pintype "passive"))
      (node (ref "FL1") (pin "3") (pinfunction "PSG_3") (pintype "passive"))
      (node (ref "J7") (pin "1") (pinfunction "1_1") (pintype "bidirectional"))
      (node (ref "J7") (pin "2") (pinfunction "2_2") (pintype "bidirectional"))
      (node (ref "J8") (pin "2") (pinfunction "2_2") (pintype "bidirectional"))
      (node (ref "J8") (pin "3") (pinfunction "3_3") (pintype "bidirectional"))
    )
    (net (code "9") (name "Net-(IC5-FB)") (class "Default")
      (node (ref "IC5") (pin "5") (pinfunction "FB_5") (pintype "input"))
      (node (ref "R28") (pin "1") (pinfunction "1_1") (pintype "passive"))
      (node (ref "R30") (pin "2") (pinfunction "2_2") (pintype "passive"))
    )
    (net (code "10") (name "Net-(IC5-MODE)") (class "Default")
      (node (ref "IC5") (pin "10") (pinfunction "MODE_10") (pintype "input"))
      (node (ref "R17") (pin "1") (pinfunction "1_1") (pintype "passive"))
    )
    (net (code "11") (name "Net-(IC5-SS{slash}TR)") (class "Default")
      (node (ref "C36") (pin "1") (pinfunction "1_1") (pintype "passive"))
      (node (ref "IC5") (pin "9") (pinfunction "SS/TR_9") (pintype "input"))
    )
    (net (code "12") (name "Net-(IC6-EN)") (class "Default")
      (node (ref "IC6") (pin "13") (pinfunction "EN_13") (pintype "input"))
      (node (ref "R157") (pin "2") (pinfunction "2_2") (pintype "passive"))
      (node (ref "R83") (pin "1") (pinfunction "1_1") (pintype "passive"))
    )
    (net (code "13") (name "Net-(IC6-NR)") (class "Default")
      (node (ref "C28") (pin "2") (pinfunction "2_2") (pintype "passive"))
      (node (ref "IC6") (pin "14") (pinfunction "NR_14") (pintype "passive"))
    )
    (net (code "14") (name "Net-(LD1-A)") (class "Default")
      (node (ref "LD1") (pin "2") (pinfunction "A_2") (pintype "passive"))
      (node (ref "R106") (pin "1") (pinfunction "1_1") (pintype "passive"))
    )
    (net (code "15") (name "Net-(LD2-A)") (class "Default")
      (node (ref "LD2") (pin "2") (pinfunction "A_2") (pintype "passive"))
      (node (ref "R216") (pin "1") (pinfunction "1_1") (pintype "passive"))
    )
    (net (code "16") (name "Net-(LD4-A)") (class "Default")
      (node (ref "LD4") (pin "2") (pinfunction "A_2") (pintype "passive"))
      (node (ref "R218") (pin "1") (pinfunction "1_1") (pintype "passive"))
    )
    (net (code "17") (name "Net-(LD5-A)") (class "Default")
      (node (ref "LD5") (pin "2") (pinfunction "A_2") (pintype "passive"))
      (node (ref "R108") (pin "2") (pinfunction "2_2") (pintype "passive"))
    )
    (net (code "18") (name "Net-(LD6-A)") (class "Default")
      (node (ref "LD6") (pin "2") (pinfunction "A_2") (pintype "passive"))
      (node (ref "R109") (pin "2") (pinfunction "2_2") (pintype "passive"))
    )
    (net (code "19") (name "Net-(LD7-A)") (class "Default")
      (node (ref "LD7") (pin "2") (pinfunction "A_2") (pintype "passive"))
      (node (ref "R110") (pin "2") (pinfunction "2_2") (pintype "passive"))
    )
    (net (code "20") (name "Net-(LD9-A)") (class "Default")
      (node (ref "LD9") (pin "2") (pinfunction "A_2") (pintype "passive"))
      (node (ref "R179") (pin "1") (pinfunction "1_1") (pintype "passive"))
    )
    (net (code "21") (name "Net-(LD10-C)") (class "Default")
      (node (ref "LD10") (pin "1") (pinfunction "C_1") (pintype "passive"))
      (node (ref "R55") (pin "2") (pinfunction "2_2") (pintype "passive"))
    )
    (net (code "22") (name "Net-(LD11-A)") (class "Default")
      (node (ref "LD11") (pin "2") (pinfunction "A_2") (pintype "passive"))
      (node (ref "R180") (pin "1") (pinfunction "1_1") (pintype "passive"))
    )
    (net (code "23") (name "Net-(R105-Pad1)") (class "Default")
      (node (ref "R105") (pin "1") (pinfunction "1_1") (pintype "passive"))
      (node (ref "RT1") (pin "2") (pinfunction "2_2") (pintype "passive"))
    )
    (net (code "24") (name "Net-(T7-D)") (class "Default")
      (node (ref "R72") (pin "1") (pinfunction "1_1") (pintype "passive"))
      (node (ref "T7") (pin "3") (pinfunction "D_3") (pintype "passive"))
    )
    (net (code "25") (name "Net-(T7-G)") (class "Default")
      (node (ref "R153") (pin "2") (pinfunction "2_2") (pintype "passive"))
      (node (ref "T7") (pin "1") (pinfunction "G_1") (pintype "passive"))
    )
    (net (code "26") (name "Net-(T14-D)") (class "Default")
      (node (ref "J11") (pin "2") (pinfunction "2_2") (pintype "bidirectional"))
      (node (ref "T14") (pin "3") (pinfunction "D_3") (pintype "passive"))
    )
    (net (code "27") (name "Net-(T14-G)") (class "Default")
      (node (ref "T14") (pin "1") (pinfunction "G_1") (pintype "passive"))
      (node (ref "U1") (pin "7") (pinfunction "VOUT_7") (pintype "output"))
    )
    (net (code "28") (name "Net-(T14-S)") (class "Default")
      (node (ref "C67") (pin "1") (pinfunction "1_1") (pintype "passive"))
      (node (ref "R91") (pin "2") (pinfunction "2_2") (pintype "passive"))
      (node (ref "T14") (pin "2") (pinfunction "S_2") (pintype "passive"))
    )
    (net (code "29") (name "Net-(U1-CF)") (class "Default")
      (node (ref "C112") (pin "2") (pinfunction "2_2") (pintype "passive"))
      (node (ref "U1") (pin "2") (pinfunction "CF_2") (pintype "passive"))
    )
    (net (code "30") (name "Net-(U1-SENSE)") (class "Default")
      (node (ref "C67") (pin "2") (pinfunction "2_2") (pintype "passive"))
      (node (ref "U1") (pin "5") (pinfunction "SENSE_5") (pintype "input"))
    )
    (net (code "31") (name "Net-(U1-VAS)") (class "Default")
      (node (ref "C93") (pin "2") (pinfunction "2_2") (pintype "passive"))
      (node (ref "R57") (pin "1") (pinfunction "1_1") (pintype "passive"))
      (node (ref "R68") (pin "2") (pinfunction "2_2") (pintype "passive"))
      (node (ref "U1") (pin "3") (pinfunction "VAS_3") (pintype "input"))
    )
    (net (code "32") (name "Net-(U1-VIN)") (class "Default")
      (node (ref "R56") (pin "1") (pinfunction "1_1") (pintype "passive"))
      (node (ref "R58") (pin "2") (pinfunction "2_2") (pintype "passive"))
      (node (ref "RT1") (pin "1") (pinfunction "1_1") (pintype "passive"))
      (node (ref "U1") (pin "1") (pinfunction "VIN_1") (pintype "input"))
    )
    (net (code "33") (name "Net-(U1-~{FAULT})") (class "Default")
      (node (ref "R55") (pin "1") (pinfunction "1_1") (pintype "passive"))
      (node (ref "U1") (pin "6") (pinfunction "~{FAULT}_6") (pintype "open_collector"))
    )
    (net (code "34") (name "P2V5REF") (class "Default")
      (node (ref "C154") (pin "2") (pinfunction "2_2") (pintype "passive"))
      (node (ref "IC28") (pin "5") (pinfunction "OUTF_5") (pintype "power_in"))
      (node (ref "IC28") (pin "6") (pinfunction "OUTS_6") (pintype "input"))
    )
    (net (code "35") (name "P3V3") (class "Default")
      (node (ref "C113") (pin "2") (pinfunction "2_2") (pintype "passive"))
      (node (ref "C153") (pin "1") (pinfunction "1_1") (pintype "passive"))
      (node (ref "C42") (pin "2") (pinfunction "2_2") (pintype "passive"))
      (node (ref "IC28") (pin "4") (pinfunction "IN_4") (pintype "input"))
      (node (ref "IC30") (pin "3") (pinfunction "OUT_3") (pintype "power_in"))
      (node (ref "LD10") (pin "2") (pinfunction "A_2") (pintype "passive"))
      (node (ref "R105") (pin "2") (pinfunction "2_2") (pintype "passive"))
      (node (ref "R108") (pin "1") (pinfunction "1_1") (pintype "passive"))
      (node (ref "R56") (pin "2") (pinfunction "2_2") (pintype "passive"))
      (node (ref "R57") (pin "2") (pinfunction "2_2") (pintype "passive"))
      (node (ref "R97") (pin "1") (pinfunction "1_1") (pintype "passive"))
      (node (ref "TP3") (pin "1") (pinfunction "1_1") (pintype "bidirectional"))
      (node (ref "U1") (pin "8") (pinfunction "VDD_8") (pintype "power_in"))
    )
    (net (code "36") (name "P3V3A") (class "Default")
      (node (ref "C63") (pin "2") (pinfunction "2_2") (pintype "passive"))
      (node (ref "IC31") (pin "3") (pinfunction "OUT_3") (pintype "power_in"))
      (node (ref "R110") (pin "1") (pinfunction "1_1") (pintype "passive"))
      (node (ref "TP5") (pin "1") (pinfunction "1_1") (pintype "bidirectional"))
    )
    (net (code "37") (name "P3V3_MP") (class "Default")
      (node (ref "C102") (pin "1") (pinfunction "1_1") (pintype "passive"))
      (node (ref "IC33") (pin "5") (pinfunction "OUT_5") (pintype "power_in"))
      (node (ref "R109") (pin "1") (pinfunction "1_1") (pintype "passive"))
      (node (ref "TP4") (pin "1") (pinfunction "1_1") (pintype "bidirectional"))
    )
    (net (code "38") (name "P5V0A") (class "Default")
      (node (ref "C27") (pin "2") (pinfunction "2_2") (pintype "passive"))
      (node (ref "IC6") (pin "1") (pinfunction "OUT_1") (pintype "power_in"))
      (node (ref "IC6") (pin "20") (pinfunction "OUT_20") (pintype "power_in"))
      (node (ref "IC6") (pin "3") (pinfunction "SENSE_3") (pintype "input"))
      (node (ref "R216") (pin "2") (pinfunction "2_2") (pintype "passive"))
      (node (ref "TP16") (pin "1") (pinfunction "1_1") (pintype "bidirectional"))
    )
    (net (code "39") (name "P5V5") (class "Default")
      (node (ref "C33") (pin "2") (pinfunction "2_2") (pintype "passive"))
      (node (ref "C34") (pin "2") (pinfunction "2_2") (pintype "passive"))
      (node (ref "C35") (pin "2") (pinfunction "2_2") (pintype "passive"))
      (node (ref "C68") (pin "2") (pinfunction "2_2") (pintype "passive"))
      (node (ref "IC30") (pin "2") (pinfunction "IN_2") (pintype "input"))
      (node (ref "IC5") (pin "6") (pinfunction "VOS_6") (pintype "input"))
      (node (ref "L10") (pin "1") (pinfunction "1_1") (pintype "passive"))
      (node (ref "L9") (pin "2") (pinfunction "2_2") (pintype "passive"))
      (node (ref "R106") (pin "2") (pinfunction "2_2") (pintype "passive"))
      (node (ref "R28") (pin "2") (pinfunction "2_2") (pintype "passive"))
      (node (ref "TP1") (pin "1") (pinfunction "1_1") (pintype "bidirectional"))
    )
    (net (code "40") (name "P5V5A") (class "Default")
      (node (ref "C97") (pin "2") (pinfunction "2_2") (pintype "passive"))
      (node (ref "IC31") (pin "2") (pinfunction "IN_2") (pintype "input"))
    )
    (net (code "41") (name "P12V0") (class "Default")
      (node (ref "C99") (pin "2") (pinfunction "2_2") (pintype "passive"))
      (node (ref "R179") (pin "2") (pinfunction "2_2") (pintype "passive"))
      (node (ref "R51") (pin "2") (pinfunction "2_2") (pintype "passive"))
      (node (ref "T6") (pin "1") (pinfunction "S_1") (pintype "passive"))
      (node (ref "T6") (pin "2") (pinfunction "S_2") (pintype "passive"))
      (node (ref "T6") (pin "3") (pinfunction "S_3") (pintype "passive"))
    )
    (net (code "42") (name "P12V0F") (class "Default")
      (node (ref "C38") (pin "2") (pinfunction "2_2") (pintype "passive"))
      (node (ref "IC5") (pin "1") (pinfunction "VIN_1") (pintype "input"))
      (node (ref "IC5") (pin "8") (pinfunction "EN_8") (pintype "input"))
      (node (ref "L8") (pin "2") (pinfunction "2_2") (pintype "passive"))
      (node (ref "R17") (pin "2") (pinfunction "2_2") (pintype "passive"))
    )
    (net (code "43") (name "P12V0_SW") (class "Default")
      (node (ref "C101") (pin "2") (pinfunction "2_2") (pintype "passive"))
      (node (ref "C114") (pin "2") (pinfunction "2_2") (pintype "passive"))
      (node (ref "C37") (pin "2") (pinfunction "2_2") (pintype "passive"))
      (node (ref "C80") (pin "2") (pinfunction "2_2") (pintype "passive"))
      (node (ref "C81") (pin "2") (pinfunction "2_2") (pintype "passive"))
      (node (ref "D1") (pin "1") (pinfunction "C_1") (pintype "passive"))
      (node (ref "FL1") (pin "2") (pinfunction "CB_2") (pintype "passive"))
      (node (ref "IC33") (pin "1") (pinfunction "IN_1") (pintype "input"))
      (node (ref "IC33") (pin "3") (pinfunction "EN_3") (pintype "input"))
      (node (ref "J11") (pin "1") (pinfunction "1_1") (pintype "bidirectional"))
      (node (ref "L8") (pin "1") (pinfunction "1_1") (pintype "passive"))
      (node (ref "R218") (pin "2") (pinfunction "2_2") (pintype "passive"))
      (node (ref "T6") (pin "5") (pinfunction "D_5") (pintype "passive"))
      (node (ref "T6") (pin "6") (pinfunction "D_6") (pintype "passive"))
      (node (ref "T6") (pin "7") (pinfunction "D_7") (pintype "passive"))
      (node (ref "T6") (pin "8") (pinfunction "D_8") (pintype "passive"))
      (node (ref "TP18") (pin "1") (pinfunction "1_1") (pintype "bidirectional"))
    )
    (net (code "44") (name "P48V0") (class "Default")
      (node (ref "R180") (pin "2") (pinfunction "2_2") (pintype "passive"))
      (node (ref "TP10") (pin "1") (pinfunction "1_1") (pintype "bidirectional"))
    )
    (net (code "45") (name "unconnected-(IC6-0P1V-Pad12)") (class "Default")
      (node (ref "IC6") (pin "12") (pinfunction "0P1V_12") (pintype "input+no_connect"))
    )
    (net (code "46") (name "unconnected-(IC6-0P4V-Pad10)") (class "Default")
      (node (ref "IC6") (pin "10") (pinfunction "0P4V_10") (pintype "input+no_connect"))
    )
    (net (code "47") (name "unconnected-(IC6-0P8V-Pad9)") (class "Default")
      (node (ref "IC6") (pin "9") (pinfunction "0P8V_9") (pintype "input+no_connect"))
    )
    (net (code "48") (name "unconnected-(IC6-6P4V1-Pad5)") (class "Default")
      (node (ref "IC6") (pin "5") (pinfunction "6P4V1_5") (pintype "input+no_connect"))
    )
    (net (code "49") (name "unconnected-(IC6-6P4V2-Pad4)") (class "Default")
      (node (ref "IC6") (pin "4") (pinfunction "6P4V2_4") (pintype "input+no_connect"))
    )
    (net (code "50") (name "unconnected-(IC33-BYP-Pad4)") (class "Default")
      (node (ref "IC33") (pin "4") (pinfunction "BYP_4") (pintype "passive+no_connect"))
    )
  )
)
